# JetsonBreakout_SoC_1_0_EY.net
KiCad netlist of a schematic drawn in Altium Designer
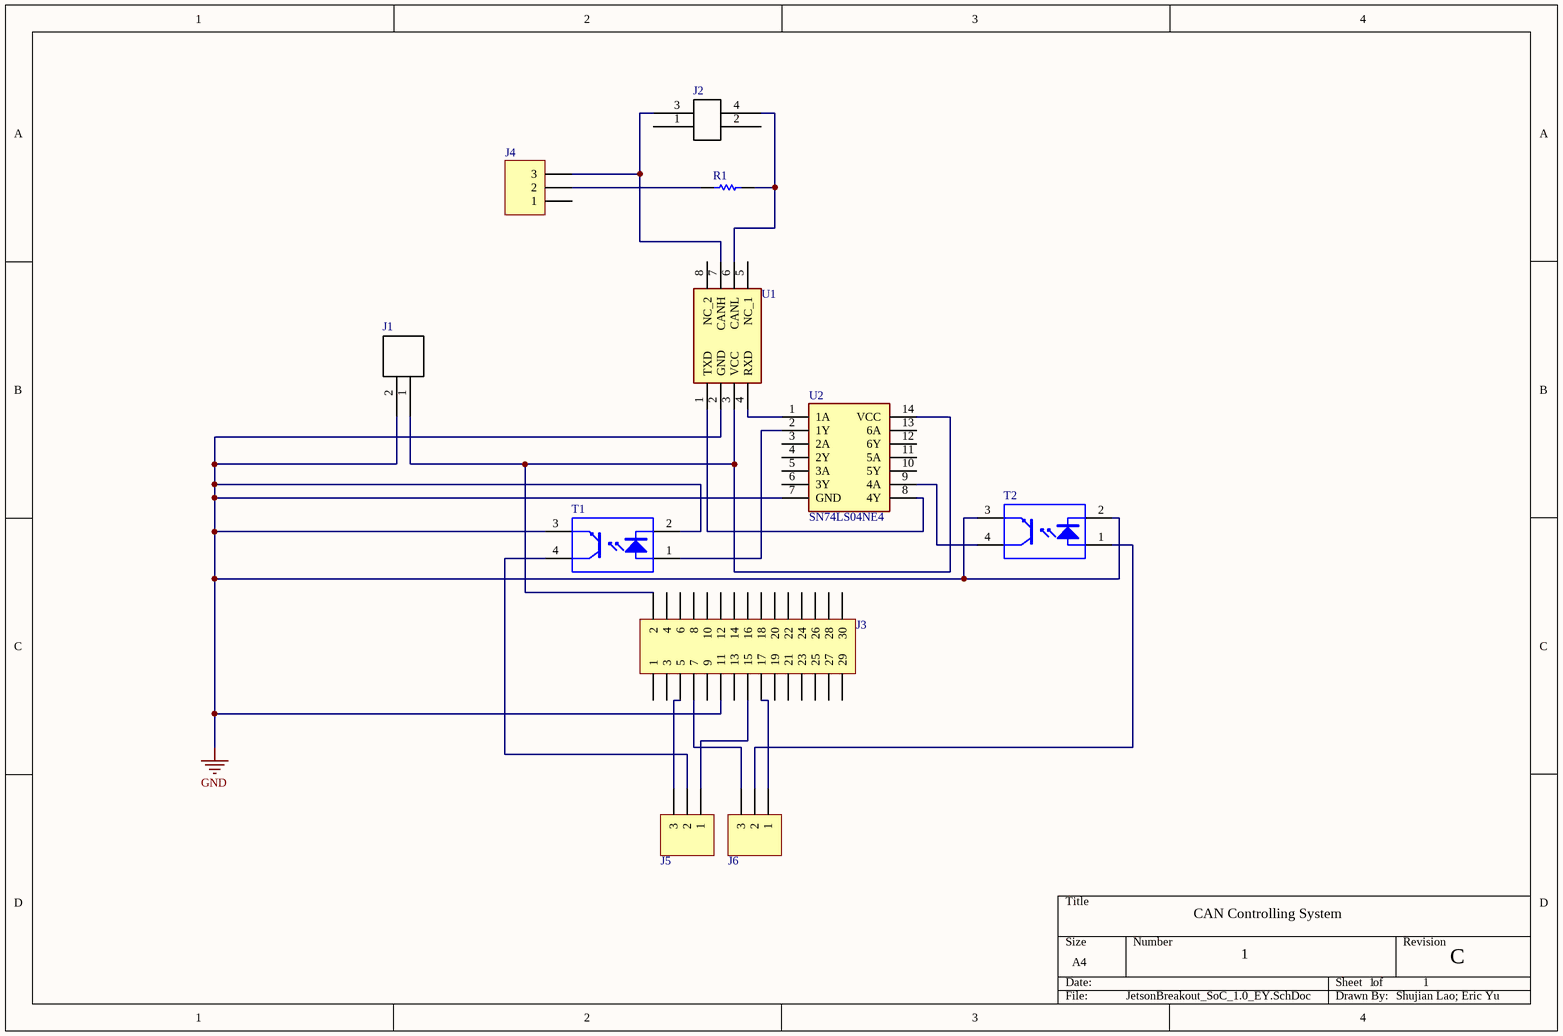
[diagram p0: JetsonBreakout_SoC_1.0_EY.SchDoc]

(export (version "E")
  (design (tool "Eeschema 10.0.6"))
  (components
    (comp (ref "J1")
      (value "~")
      (footprint "1510482204")
      (libsource (lib "Husky Robotics Standard Library 2019-2020") (part "Molex 6.5MM  power connector"))
    )
    (comp (ref "J2")
      (value "~")
      (footprint "0430450427")
      (description "Molex micro-fit 3.0, P/N 0430450427")
      (libsource (lib "Husky Robotics Standard Library 2019-2020") (part "Molex micro-fit 4-pin (dual row schematic)"))
    )
    (comp (ref "J3")
      (value "~")
      (footprint "HDR2X15")
      (description "Header, 15-Pin, Dual row")
      (fields (field (name "PUBLISHER") "Altium Limited"))
      (libsource (lib "Miscellaneous Connectors") (part "Header 15X2"))
    )
    (comp (ref "J4")
      (value "~")
      (footprint "HDR1X3")
      (description "Header, 3-Pin")
      (fields (field (name "PUBLISHER") "Altium Limited"))
      (libsource (lib "") (part "Header 3_1"))
    )
    (comp (ref "J5")
      (value "~")
      (footprint "HDR1X3")
      (description "Header, 3-Pin")
      (fields (field (name "PUBLISHER") "Altium Limited"))
      (libsource (lib "Miscellaneous Connectors") (part "Header 3"))
    )
    (comp (ref "J6")
      (value "~")
      (footprint "HDR1X3")
      (description "Header, 3-Pin")
      (fields (field (name "PUBLISHER") "Altium Limited"))
      (libsource (lib "Miscellaneous Connectors") (part "Header 3"))
    )
    (comp (ref "R1")
      (value "~")
      (footprint "RESC0805(2012)_N")
      (description "120R 0.125W 5% 0805 (2012 Metric)  SMD")
      (fields (field (name "TOLERANCE") "5 %") (field (name "POWER") "0.125 W"))
      (libsource (lib "Husky Robotics Standard Library 2019-2020") (part "120R 5% 0805"))
    )
    (comp (ref "T1")
      (value "~")
      (footprint "FAIR-MDIP-4_V")
      (fields (field (name "MANUFACTURER") "Fairchild Semiconductor"))
      (libsource (lib "Altium Content Vault") (part "OPTO-AKEC-4"))
    )
    (comp (ref "T2")
      (value "~")
      (footprint "FAIR-MDIP-4_V")
      (fields (field (name "MANUFACTURER") "Fairchild Semiconductor"))
      (libsource (lib "Altium Content Vault") (part "OPTO-AKEC-4"))
    )
    (comp (ref "U1")
      (value "~")
      (footprint "SamacSys:SOIC127P600X175-8N")
      (description "Integrated Circuit")
      (fields
        (field (name "MANUFACTURER_PART_NUMBER") "TCAN332DR")
        (field (name "MOUSER PART NUMBER") "595-TCAN332DR")
      )
      (libsource (lib "*") (part "TCAN332DR"))
    )
    (comp (ref "U2")
      (value "SN74LS04NE4")
      (footprint "SamacSys:DIP794W53P254L1930H508Q14N")
      (description "Integrated Circuit")
      (fields (field (name "MOUSER PART NUMBER") "595-SN74LS04NE4"))
      (libsource (lib "*") (part "SN74LS04NE4"))
    )
  )
  (nets
    (net (code "1") (name "GND") (class "Default")
      (node (ref "J1") (pin "2") (pintype "passive"))
      (node (ref "J3") (pin "11") (pinfunction "11_11") (pintype "passive"))
      (node (ref "T1") (pin "2") (pinfunction "CATHODE_2") (pintype "passive"))
      (node (ref "T1") (pin "3") (pinfunction "EMITTER_3") (pintype "passive"))
      (node (ref "T2") (pin "2") (pinfunction "CATHODE_2") (pintype "passive"))
      (node (ref "T2") (pin "3") (pinfunction "EMITTER_3") (pintype "passive"))
      (node (ref "U1") (pin "2") (pinfunction "GND_2") (pintype "passive"))
      (node (ref "U2") (pin "7") (pinfunction "GND_7") (pintype "passive"))
    )
    (net (code "2") (name "Net-(J3-Pad5)") (class "Default")
      (node (ref "J3") (pin "5") (pinfunction "5_5") (pintype "passive"))
      (node (ref "J5") (pin "3") (pinfunction "3_3") (pintype "passive"))
    )
    (net (code "3") (name "Net-(J3-Pad7)") (class "Default")
      (node (ref "J3") (pin "7") (pinfunction "7_7") (pintype "passive"))
      (node (ref "J6") (pin "3") (pinfunction "3_3") (pintype "passive"))
    )
    (net (code "4") (name "Net-(J3-Pad15)") (class "Default")
      (node (ref "J3") (pin "15") (pinfunction "15_15") (pintype "passive"))
      (node (ref "J5") (pin "1") (pinfunction "1_1") (pintype "passive"))
    )
    (net (code "5") (name "Net-(J3-Pad17)") (class "Default")
      (node (ref "J3") (pin "17") (pinfunction "17_17") (pintype "passive"))
      (node (ref "J6") (pin "1") (pinfunction "1_1") (pintype "passive"))
    )
    (net (code "6") (name "Net-(J4-Pad2)") (class "Default")
      (node (ref "J4") (pin "2") (pinfunction "2_2") (pintype "passive"))
      (node (ref "R1") (pin "1") (pinfunction "1_1") (pintype "passive"))
    )
    (net (code "7") (name "Net-(T1-ANODE)") (class "Default")
      (node (ref "T1") (pin "1") (pinfunction "ANODE_1") (pintype "passive"))
      (node (ref "U2") (pin "2") (pinfunction "1Y_2") (pintype "passive"))
    )
    (net (code "8") (name "Net-(T1-COLLECTOR)") (class "Default")
      (node (ref "J5") (pin "2") (pinfunction "2_2") (pintype "passive"))
      (node (ref "T1") (pin "4") (pinfunction "COLLECTOR_4") (pintype "passive"))
    )
    (net (code "9") (name "Net-(T2-ANODE)") (class "Default")
      (node (ref "J6") (pin "2") (pinfunction "2_2") (pintype "passive"))
      (node (ref "T2") (pin "1") (pinfunction "ANODE_1") (pintype "passive"))
    )
    (net (code "10") (name "Net-(T2-COLLECTOR)") (class "Default")
      (node (ref "T2") (pin "4") (pinfunction "COLLECTOR_4") (pintype "passive"))
      (node (ref "U2") (pin "9") (pinfunction "4A_9") (pintype "passive"))
    )
    (net (code "11") (name "Net-(U1-CANH)") (class "Default")
      (node (ref "J2") (pin "3") (pintype "passive"))
      (node (ref "J4") (pin "3") (pinfunction "3_3") (pintype "passive"))
      (node (ref "U1") (pin "7") (pinfunction "CANH_7") (pintype "passive"))
    )
    (net (code "12") (name "Net-(U1-CANL)") (class "Default")
      (node (ref "J2") (pin "4") (pintype "passive"))
      (node (ref "R1") (pin "2") (pinfunction "2_2") (pintype "passive"))
      (node (ref "U1") (pin "6") (pinfunction "CANL_6") (pintype "passive"))
    )
    (net (code "13") (name "Net-(U1-RXD)") (class "Default")
      (node (ref "U1") (pin "4") (pinfunction "RXD_4") (pintype "passive"))
      (node (ref "U2") (pin "1") (pinfunction "1A_1") (pintype "passive"))
    )
    (net (code "14") (name "Net-(U1-TXD)") (class "Default")
      (node (ref "U1") (pin "1") (pinfunction "TXD_1") (pintype "passive"))
      (node (ref "U2") (pin "8") (pinfunction "4Y_8") (pintype "passive"))
    )
    (net (code "15") (name "Net-(U1-VCC)") (class "Default")
      (node (ref "J1") (pin "1") (pintype "passive"))
      (node (ref "J3") (pin "2") (pinfunction "2_2") (pintype "passive"))
      (node (ref "U1") (pin "3") (pinfunction "VCC_3") (pintype "passive"))
      (node (ref "U2") (pin "14") (pinfunction "VCC_14") (pintype "passive"))
    )
    (net (code "16") (name "unconnected-(J2-Pad1)") (class "Default")
      (node (ref "J2") (pin "1") (pintype "passive"))
    )
    (net (code "17") (name "unconnected-(J2-Pad2)") (class "Default")
      (node (ref "J2") (pin "2") (pintype "passive"))
    )
    (net (code "18") (name "unconnected-(J3-Pad1)") (class "Default")
      (node (ref "J3") (pin "1") (pinfunction "1_1") (pintype "passive"))
    )
    (net (code "19") (name "unconnected-(J3-Pad3)") (class "Default")
      (node (ref "J3") (pin "3") (pinfunction "3_3") (pintype "passive"))
    )
    (net (code "20") (name "unconnected-(J3-Pad4)") (class "Default")
      (node (ref "J3") (pin "4") (pinfunction "4_4") (pintype "passive"))
    )
    (net (code "21") (name "unconnected-(J3-Pad6)") (class "Default")
      (node (ref "J3") (pin "6") (pinfunction "6_6") (pintype "passive"))
    )
    (net (code "22") (name "unconnected-(J3-Pad8)") (class "Default")
      (node (ref "J3") (pin "8") (pinfunction "8_8") (pintype "passive"))
    )
    (net (code "23") (name "unconnected-(J3-Pad9)") (class "Default")
      (node (ref "J3") (pin "9") (pinfunction "9_9") (pintype "passive"))
    )
    (net (code "24") (name "unconnected-(J3-Pad10)") (class "Default")
      (node (ref "J3") (pin "10") (pinfunction "10_10") (pintype "passive"))
    )
    (net (code "25") (name "unconnected-(J3-Pad12)") (class "Default")
      (node (ref "J3") (pin "12") (pinfunction "12_12") (pintype "passive"))
    )
    (net (code "26") (name "unconnected-(J3-Pad13)") (class "Default")
      (node (ref "J3") (pin "13") (pinfunction "13_13") (pintype "passive"))
    )
    (net (code "27") (name "unconnected-(J3-Pad14)") (class "Default")
      (node (ref "J3") (pin "14") (pinfunction "14_14") (pintype "passive"))
    )
    (net (code "28") (name "unconnected-(J3-Pad16)") (class "Default")
      (node (ref "J3") (pin "16") (pinfunction "16_16") (pintype "passive"))
    )
    (net (code "29") (name "unconnected-(J3-Pad18)") (class "Default")
      (node (ref "J3") (pin "18") (pinfunction "18_18") (pintype "passive"))
    )
    (net (code "30") (name "unconnected-(J3-Pad19)") (class "Default")
      (node (ref "J3") (pin "19") (pinfunction "19_19") (pintype "passive"))
    )
    (net (code "31") (name "unconnected-(J3-Pad20)") (class "Default")
      (node (ref "J3") (pin "20") (pinfunction "20_20") (pintype "passive"))
    )
    (net (code "32") (name "unconnected-(J3-Pad21)") (class "Default")
      (node (ref "J3") (pin "21") (pinfunction "21_21") (pintype "passive"))
    )
    (net (code "33") (name "unconnected-(J3-Pad22)") (class "Default")
      (node (ref "J3") (pin "22") (pinfunction "22_22") (pintype "passive"))
    )
    (net (code "34") (name "unconnected-(J3-Pad23)") (class "Default")
      (node (ref "J3") (pin "23") (pinfunction "23_23") (pintype "passive"))
    )
    (net (code "35") (name "unconnected-(J3-Pad24)") (class "Default")
      (node (ref "J3") (pin "24") (pinfunction "24_24") (pintype "passive"))
    )
    (net (code "36") (name "unconnected-(J3-Pad25)") (class "Default")
      (node (ref "J3") (pin "25") (pinfunction "25_25") (pintype "passive"))
    )
    (net (code "37") (name "unconnected-(J3-Pad26)") (class "Default")
      (node (ref "J3") (pin "26") (pinfunction "26_26") (pintype "passive"))
    )
    (net (code "38") (name "unconnected-(J3-Pad27)") (class "Default")
      (node (ref "J3") (pin "27") (pinfunction "27_27") (pintype "passive"))
    )
    (net (code "39") (name "unconnected-(J3-Pad28)") (class "Default")
      (node (ref "J3") (pin "28") (pinfunction "28_28") (pintype "passive"))
    )
    (net (code "40") (name "unconnected-(J3-Pad29)") (class "Default")
      (node (ref "J3") (pin "29") (pinfunction "29_29") (pintype "passive"))
    )
    (net (code "41") (name "unconnected-(J3-Pad30)") (class "Default")
      (node (ref "J3") (pin "30") (pinfunction "30_30") (pintype "passive"))
    )
    (net (code "42") (name "unconnected-(J4-Pad1)") (class "Default")
      (node (ref "J4") (pin "1") (pinfunction "1_1") (pintype "passive"))
    )
    (net (code "43") (name "unconnected-(U1-NC_1-Pad5)") (class "Default")
      (node (ref "U1") (pin "5") (pinfunction "NC_1_5") (pintype "passive"))
    )
    (net (code "44") (name "unconnected-(U1-NC_2-Pad8)") (class "Default")
      (node (ref "U1") (pin "8") (pinfunction "NC_2_8") (pintype "passive"))
    )
    (net (code "45") (name "unconnected-(U2-2A-Pad3)") (class "Default")
      (node (ref "U2") (pin "3") (pinfunction "2A_3") (pintype "passive"))
    )
    (net (code "46") (name "unconnected-(U2-2Y-Pad4)") (class "Default")
      (node (ref "U2") (pin "4") (pinfunction "2Y_4") (pintype "passive"))
    )
    (net (code "47") (name "unconnected-(U2-3A-Pad5)") (class "Default")
      (node (ref "U2") (pin "5") (pinfunction "3A_5") (pintype "passive"))
    )
    (net (code "48") (name "unconnected-(U2-3Y-Pad6)") (class "Default")
      (node (ref "U2") (pin "6") (pinfunction "3Y_6") (pintype "passive"))
    )
    (net (code "49") (name "unconnected-(U2-5A-Pad11)") (class "Default")
      (node (ref "U2") (pin "11") (pinfunction "5A_11") (pintype "passive"))
    )
    (net (code "50") (name "unconnected-(U2-5Y-Pad10)") (class "Default")
      (node (ref "U2") (pin "10") (pinfunction "5Y_10") (pintype "passive"))
    )
    (net (code "51") (name "unconnected-(U2-6A-Pad13)") (class "Default")
      (node (ref "U2") (pin "13") (pinfunction "6A_13") (pintype "passive"))
    )
    (net (code "52") (name "unconnected-(U2-6Y-Pad12)") (class "Default")
      (node (ref "U2") (pin "12") (pinfunction "6Y_12") (pintype "passive"))
    )
  )
)
